# MCU.net
KiCad netlist of a schematic drawn in Altium Designer
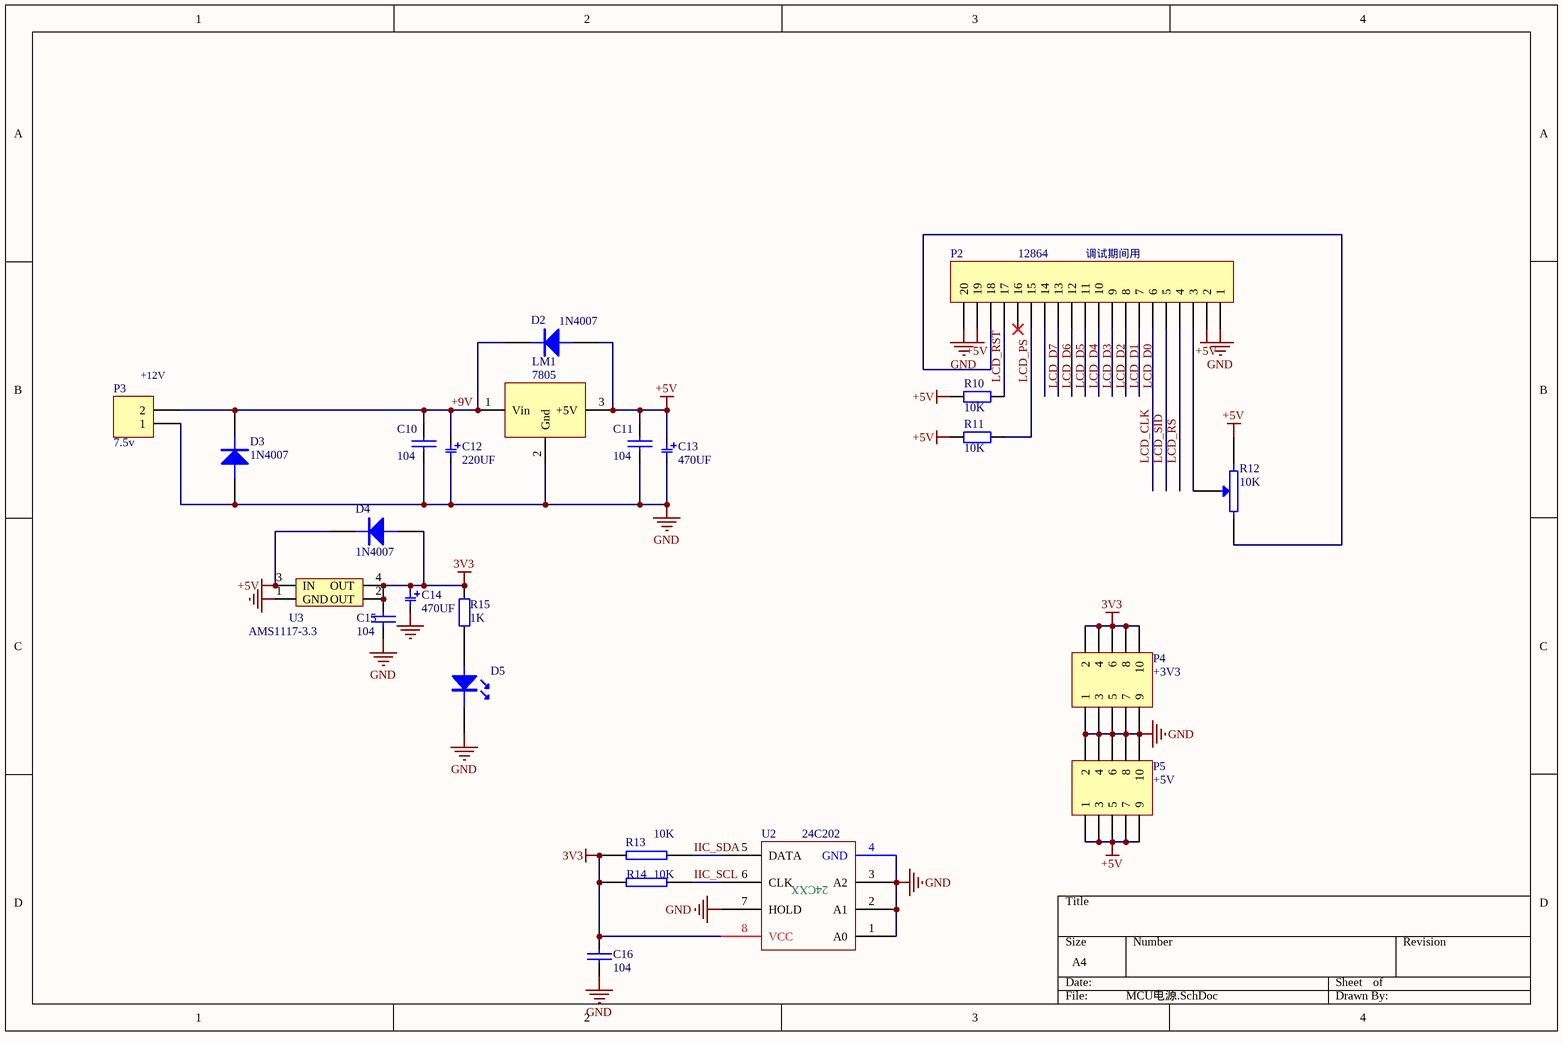
[diagram p0: MCU电源.SchDoc]

(export (version "E")
  (design (tool "Eeschema 10.0.6"))
  (components
    (comp (ref "C10")
      (value "104")
      (footprint "1206")
      (description "Capacitor")
      (libsource (lib "电容") (part "普通电容"))
    )
    (comp (ref "C11")
      (value "104")
      (footprint "1206")
      (description "Capacitor")
      (libsource (lib "电容") (part "普通电容"))
    )
    (comp (ref "C12") (value "220UF") (footprint "C220U") (libsource (lib "电容") (part "ECAP")))
    (comp (ref "C13") (value "470UF") (footprint "C220U") (libsource (lib "电容") (part "ECAP")))
    (comp (ref "C14") (value "470UF") (footprint "C220U") (libsource (lib "电容") (part "ECAP")))
    (comp (ref "C15")
      (value "104")
      (footprint "1206")
      (description "Capacitor")
      (libsource (lib "电容") (part "普通电容"))
    )
    (comp (ref "C16")
      (value "104")
      (footprint "1206")
      (description "Capacitor")
      (libsource (lib "*") (part "CAP"))
    )
    (comp (ref "D2")
      (value "1N4007")
      (footprint "7227")
      (description "Diode")
      (libsource (lib "Miscellaneous Devices") (part "DIODE"))
    )
    (comp (ref "D3")
      (value "1N4007")
      (footprint "7227")
      (description "Diode")
      (libsource (lib "Miscellaneous Devices") (part "DIODE"))
    )
    (comp (ref "D4")
      (value "1N4007")
      (footprint "7227")
      (description "Diode")
      (libsource (lib "Miscellaneous Devices") (part "DIODE"))
    )
    (comp (ref "D5") (value "~") (footprint "李建国1:LED") (libsource (lib "二极管") (part "发光二极管")))
    (comp (ref "LM1") (value "7805") (footprint "TO-220") (libsource (lib "单片机及相关") (part "LM7805CT")))
    (comp (ref "P2")
      (value "12864")
      (footprint "HDR1X20")
      (description "Header, 20-Pin")
      (fields (field (name "PUBLISHER") "Altium Limited"))
      (libsource (lib "Miscellaneous Connectors") (part "Header 20"))
    )
    (comp (ref "P3")
      (value "7.5v")
      (footprint "OUT_CJ")
      (description "Header, 2-Pin")
      (fields (field (name "PUBLISHER") "Altium Limited"))
      (libsource (lib "Miscellaneous Connectors") (part "Header 2"))
    )
    (comp (ref "P4")
      (value "+3V3")
      (footprint "HDR2X5")
      (description "Header, 5-Pin, Dual row")
      (fields (field (name "PUBLISHER") "Altium Limited"))
      (libsource (lib "Miscellaneous Connectors") (part "Header 5X2"))
    )
    (comp (ref "P5")
      (value "+5V")
      (footprint "HDR2X5")
      (description "Header, 5-Pin, Dual row")
      (fields (field (name "PUBLISHER") "Altium Limited"))
      (libsource (lib "Miscellaneous Connectors") (part "Header 5X2"))
    )
    (comp (ref "R10")
      (value "10K")
      (footprint "1206")
      (description "Resistor")
      (fields (field (name "PUBLISHER") "Altium Limited"))
      (libsource (lib "Miscellaneous Devices") (part "Res2"))
    )
    (comp (ref "R11")
      (value "10K")
      (footprint "1206")
      (description "Resistor")
      (fields (field (name "PUBLISHER") "Altium Limited"))
      (libsource (lib "Miscellaneous Devices") (part "Res2"))
    )
    (comp (ref "R12")
      (value "10K")
      (footprint "VR")
      (description "Potentiometer")
      (libsource (lib "电阻") (part "RESVR"))
    )
    (comp (ref "R13") (value "10K") (footprint "1206") (libsource (lib "*") (part "RES2")))
    (comp (ref "R14") (value "10K") (footprint "1206") (libsource (lib "*") (part "RES2")))
    (comp (ref "R15")
      (value "1K")
      (footprint "1206")
      (description "Resistor")
      (fields (field (name "PUBLISHER") "Altium Limited"))
      (libsource (lib "") (part "Res2_1"))
    )
    (comp (ref "U2") (value "24C202") (footprint "SO-8") (libsource (lib "单片机及相关") (part "24CXX")))
    (comp (ref "U3")
      (value "AMS1117-3.3")
      (footprint "AMS1117")
      (libsource (lib "MiniSTM32 V3.0封装库") (part "AMS1117"))
    )
  )
  (nets
    (net (code "1") (name "+5V") (class "Default")
      (node (ref "C11") (pin "2") (pinfunction "2_2") (pintype "passive"))
      (node (ref "C13") (pin "1") (pintype "passive"))
      (node (ref "D2") (pin "1") (pinfunction "A_1") (pintype "passive"))
      (node (ref "D4") (pin "2") (pinfunction "K_2") (pintype "passive"))
      (node (ref "LM1") (pin "3") (pinfunction "+5V_3") (pintype "passive"))
      (node (ref "P2") (pin "19") (pinfunction "19_19") (pintype "passive"))
      (node (ref "P2") (pin "2") (pinfunction "2_2") (pintype "passive"))
      (node (ref "P5") (pin "1") (pinfunction "1_1") (pintype "passive"))
      (node (ref "P5") (pin "3") (pinfunction "3_3") (pintype "passive"))
      (node (ref "P5") (pin "5") (pinfunction "5_5") (pintype "passive"))
      (node (ref "P5") (pin "7") (pinfunction "7_7") (pintype "passive"))
      (node (ref "P5") (pin "9") (pinfunction "9_9") (pintype "passive"))
      (node (ref "R10") (pin "1") (pinfunction "1_1") (pintype "passive"))
      (node (ref "R11") (pin "1") (pinfunction "1_1") (pintype "passive"))
      (node (ref "R12") (pin "2") (pinfunction "2_2") (pintype "passive"))
      (node (ref "U3") (pin "3") (pinfunction "IN_3") (pintype "passive"))
    )
    (net (code "2") (name "/+9V") (class "Default")
      (node (ref "C10") (pin "2") (pinfunction "2_2") (pintype "passive"))
      (node (ref "C12") (pin "1") (pintype "passive"))
      (node (ref "D2") (pin "2") (pinfunction "K_2") (pintype "passive"))
      (node (ref "D3") (pin "2") (pinfunction "K_2") (pintype "passive"))
      (node (ref "LM1") (pin "1") (pinfunction "Vin_1") (pintype "passive"))
      (node (ref "P3") (pin "2") (pinfunction "2_2") (pintype "passive"))
    )
    (net (code "3") (name "/IIC_SCL") (class "Default")
      (node (ref "R14") (pin "2") (pinfunction "2_2") (pintype "passive"))
      (node (ref "U2") (pin "6") (pinfunction "CLK_6") (pintype "passive"))
    )
    (net (code "4") (name "/IIC_SDA") (class "Default")
      (node (ref "R13") (pin "2") (pinfunction "2_2") (pintype "passive"))
      (node (ref "U2") (pin "5") (pinfunction "DATA_5") (pintype "passive"))
    )
    (net (code "5") (name "/LCD_CLK") (class "Default")
      (node (ref "P2") (pin "6") (pinfunction "6_6") (pintype "passive"))
    )
    (net (code "6") (name "/LCD_D0") (class "Default")
      (node (ref "P2") (pin "7") (pinfunction "7_7") (pintype "passive"))
    )
    (net (code "7") (name "/LCD_D1") (class "Default")
      (node (ref "P2") (pin "8") (pinfunction "8_8") (pintype "passive"))
    )
    (net (code "8") (name "/LCD_D2") (class "Default")
      (node (ref "P2") (pin "9") (pinfunction "9_9") (pintype "passive"))
    )
    (net (code "9") (name "/LCD_D3") (class "Default")
      (node (ref "P2") (pin "10") (pinfunction "10_10") (pintype "passive"))
    )
    (net (code "10") (name "/LCD_D4") (class "Default")
      (node (ref "P2") (pin "11") (pinfunction "11_11") (pintype "passive"))
    )
    (net (code "11") (name "/LCD_D5") (class "Default")
      (node (ref "P2") (pin "12") (pinfunction "12_12") (pintype "passive"))
    )
    (net (code "12") (name "/LCD_D6") (class "Default")
      (node (ref "P2") (pin "13") (pinfunction "13_13") (pintype "passive"))
    )
    (net (code "13") (name "/LCD_D7") (class "Default")
      (node (ref "P2") (pin "14") (pinfunction "14_14") (pintype "passive"))
    )
    (net (code "14") (name "/LCD_PS") (class "Default")
      (node (ref "P2") (pin "15") (pinfunction "15_15") (pintype "passive"))
      (node (ref "R11") (pin "2") (pinfunction "2_2") (pintype "passive"))
    )
    (net (code "15") (name "/LCD_RS") (class "Default")
      (node (ref "P2") (pin "4") (pinfunction "4_4") (pintype "passive"))
    )
    (net (code "16") (name "/LCD_RST") (class "Default")
      (node (ref "P2") (pin "17") (pinfunction "17_17") (pintype "passive"))
      (node (ref "R10") (pin "2") (pinfunction "2_2") (pintype "passive"))
    )
    (net (code "17") (name "/LCD_SID") (class "Default")
      (node (ref "P2") (pin "5") (pinfunction "5_5") (pintype "passive"))
    )
    (net (code "18") (name "3V3") (class "Default")
      (node (ref "C14") (pin "1") (pintype "passive"))
      (node (ref "C15") (pin "2") (pinfunction "2_2") (pintype "passive"))
      (node (ref "C16") (pin "2") (pinfunction "2_2") (pintype "passive"))
      (node (ref "D4") (pin "1") (pinfunction "A_1") (pintype "passive"))
      (node (ref "P4") (pin "10") (pinfunction "10_10") (pintype "passive"))
      (node (ref "P4") (pin "2") (pinfunction "2_2") (pintype "passive"))
      (node (ref "P4") (pin "4") (pinfunction "4_4") (pintype "passive"))
      (node (ref "P4") (pin "6") (pinfunction "6_6") (pintype "passive"))
      (node (ref "P4") (pin "8") (pinfunction "8_8") (pintype "passive"))
      (node (ref "R13") (pin "1") (pinfunction "1_1") (pintype "passive"))
      (node (ref "R14") (pin "1") (pinfunction "1_1") (pintype "passive"))
      (node (ref "R15") (pin "1") (pinfunction "1_1") (pintype "passive"))
      (node (ref "U2") (pin "8") (pinfunction "VCC_8") (pintype "passive"))
      (node (ref "U3") (pin "2") (pinfunction "OUT_2") (pintype "passive"))
      (node (ref "U3") (pin "4") (pinfunction "OUT_4") (pintype "passive"))
    )
    (net (code "19") (name "GND") (class "Default")
      (node (ref "C10") (pin "1") (pinfunction "1_1") (pintype "passive"))
      (node (ref "C11") (pin "1") (pinfunction "1_1") (pintype "passive"))
      (node (ref "C12") (pin "2") (pintype "passive"))
      (node (ref "C13") (pin "2") (pintype "passive"))
      (node (ref "C14") (pin "2") (pintype "passive"))
      (node (ref "C15") (pin "1") (pinfunction "1_1") (pintype "passive"))
      (node (ref "C16") (pin "1") (pinfunction "1_1") (pintype "passive"))
      (node (ref "D3") (pin "1") (pinfunction "A_1") (pintype "passive"))
      (node (ref "D5") (pin "K") (pinfunction "2_K") (pintype "passive"))
      (node (ref "LM1") (pin "2") (pinfunction "Gnd_2") (pintype "passive"))
      (node (ref "P2") (pin "1") (pinfunction "1_1") (pintype "passive"))
      (node (ref "P2") (pin "20") (pinfunction "20_20") (pintype "passive"))
      (node (ref "P3") (pin "1") (pinfunction "1_1") (pintype "passive"))
      (node (ref "P4") (pin "1") (pinfunction "1_1") (pintype "passive"))
      (node (ref "P4") (pin "3") (pinfunction "3_3") (pintype "passive"))
      (node (ref "P4") (pin "5") (pinfunction "5_5") (pintype "passive"))
      (node (ref "P4") (pin "7") (pinfunction "7_7") (pintype "passive"))
      (node (ref "P4") (pin "9") (pinfunction "9_9") (pintype "passive"))
      (node (ref "P5") (pin "10") (pinfunction "10_10") (pintype "passive"))
      (node (ref "P5") (pin "2") (pinfunction "2_2") (pintype "passive"))
      (node (ref "P5") (pin "4") (pinfunction "4_4") (pintype "passive"))
      (node (ref "P5") (pin "6") (pinfunction "6_6") (pintype "passive"))
      (node (ref "P5") (pin "8") (pinfunction "8_8") (pintype "passive"))
      (node (ref "U2") (pin "1") (pinfunction "A0_1") (pintype "passive"))
      (node (ref "U2") (pin "2") (pinfunction "A1_2") (pintype "passive"))
      (node (ref "U2") (pin "3") (pinfunction "A2_3") (pintype "passive"))
      (node (ref "U2") (pin "4") (pinfunction "GND_4") (pintype "passive"))
      (node (ref "U2") (pin "7") (pinfunction "HOLD_7") (pintype "passive"))
      (node (ref "U3") (pin "1") (pinfunction "GND_1") (pintype "passive"))
    )
    (net (code "20") (name "Net-(D5-1)") (class "Default")
      (node (ref "D5") (pin "A") (pinfunction "1_A") (pintype "passive"))
      (node (ref "R15") (pin "2") (pinfunction "2_2") (pintype "passive"))
    )
    (net (code "21") (name "Net-(P2-Pad18)") (class "Default")
      (node (ref "P2") (pin "18") (pinfunction "18_18") (pintype "passive"))
      (node (ref "R12") (pin "1") (pinfunction "1_1") (pintype "passive"))
    )
    (net (code "22") (name "Net-(R12-W)") (class "Default")
      (node (ref "P2") (pin "3") (pinfunction "3_3") (pintype "passive"))
      (node (ref "R12") (pin "3") (pinfunction "W_3") (pintype "passive"))
    )
    (net (code "23") (name "unconnected-(P2-Pad16)") (class "Default")
      (node (ref "P2") (pin "16") (pinfunction "16_16") (pintype "passive+no_connect"))
    )
  )
)
